# Balancer.net
KiCad netlist of a schematic drawn in Altium Designer
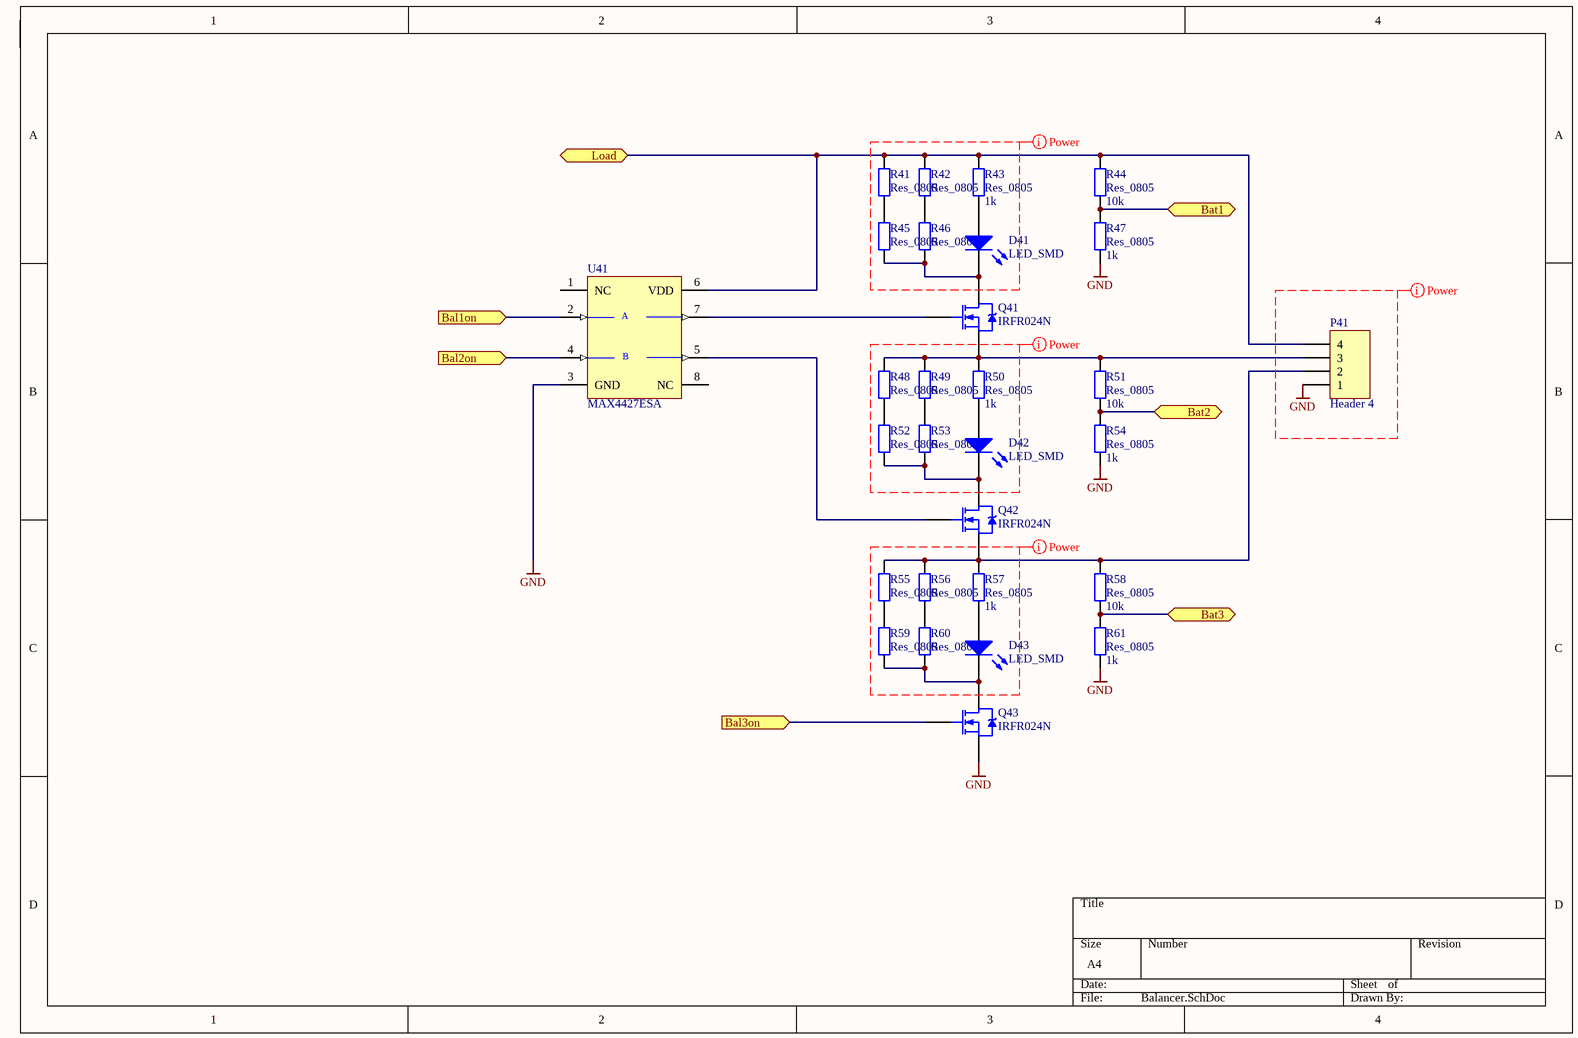
[diagram p0: Balancer.SchDoc]

(export (version "E")
  (design (tool "Eeschema 10.0.6"))
  (components
    (comp (ref "D41") (value "LED_SMD") (footprint "LED_SMD") (libsource (lib "Diodes$") (part "DIODE_48")))
    (comp (ref "D42") (value "LED_SMD") (footprint "LED_SMD") (libsource (lib "Diodes$") (part "DIODE_48")))
    (comp (ref "D43") (value "LED_SMD") (footprint "LED_SMD") (libsource (lib "Diodes$") (part "DIODE_48")))
    (comp (ref "P41") (value "Header 4") (footprint "HDR1X4") (libsource (lib "Connectors$") (part "Con_33")))
    (comp (ref "Q41")
      (value "IRFR024N")
      (footprint "TO-252AA_N")
      (description "HEXFET N-Channel Power MOSFET")
      (fields (field (name "PUBLISHER") "Altium Limited"))
      (libsource (lib "IR Discrete MOSFET - Power") (part "IRFR024N"))
    )
    (comp (ref "Q42")
      (value "IRFR024N")
      (footprint "TO-252AA_N")
      (description "HEXFET N-Channel Power MOSFET")
      (fields (field (name "PUBLISHER") "Altium Limited"))
      (libsource (lib "IR Discrete MOSFET - Power") (part "IRFR024N"))
    )
    (comp (ref "Q43")
      (value "IRFR024N")
      (footprint "TO-252AA_N")
      (description "HEXFET N-Channel Power MOSFET")
      (fields (field (name "PUBLISHER") "Altium Limited"))
      (libsource (lib "IR Discrete MOSFET - Power") (part "IRFR024N"))
    )
    (comp (ref "R41") (value "Res_0805") (footprint "_0805") (libsource (lib "Resistors$") (part "Res_6")))
    (comp (ref "R42") (value "Res_0805") (footprint "_0805") (libsource (lib "Resistors$") (part "Res_6")))
    (comp (ref "R43")
      (value "Res_0805")
      (footprint "_0805")
      (fields (field (name "ALTIUM_VALUE") "1k"))
      (libsource (lib "Resistors$") (part "Res_6"))
    )
    (comp (ref "R44")
      (value "Res_0805")
      (footprint "_0805")
      (fields (field (name "ALTIUM_VALUE") "10k"))
      (libsource (lib "Resistors$") (part "Res_6"))
    )
    (comp (ref "R45") (value "Res_0805") (footprint "_0805") (libsource (lib "Resistors$") (part "Res_6")))
    (comp (ref "R46") (value "Res_0805") (footprint "_0805") (libsource (lib "Resistors$") (part "Res_6")))
    (comp (ref "R47")
      (value "Res_0805")
      (footprint "_0805")
      (fields (field (name "ALTIUM_VALUE") "1k"))
      (libsource (lib "Resistors$") (part "Res_6"))
    )
    (comp (ref "R48") (value "Res_0805") (footprint "_0805") (libsource (lib "Resistors$") (part "Res_6")))
    (comp (ref "R49") (value "Res_0805") (footprint "_0805") (libsource (lib "Resistors$") (part "Res_6")))
    (comp (ref "R50")
      (value "Res_0805")
      (footprint "_0805")
      (fields (field (name "ALTIUM_VALUE") "1k"))
      (libsource (lib "Resistors$") (part "Res_6"))
    )
    (comp (ref "R51")
      (value "Res_0805")
      (footprint "_0805")
      (fields (field (name "ALTIUM_VALUE") "10k"))
      (libsource (lib "Resistors$") (part "Res_6"))
    )
    (comp (ref "R52") (value "Res_0805") (footprint "_0805") (libsource (lib "Resistors$") (part "Res_6")))
    (comp (ref "R53") (value "Res_0805") (footprint "_0805") (libsource (lib "Resistors$") (part "Res_6")))
    (comp (ref "R54")
      (value "Res_0805")
      (footprint "_0805")
      (fields (field (name "ALTIUM_VALUE") "1k"))
      (libsource (lib "Resistors$") (part "Res_6"))
    )
    (comp (ref "R55") (value "Res_0805") (footprint "_0805") (libsource (lib "Resistors$") (part "Res_6")))
    (comp (ref "R56") (value "Res_0805") (footprint "_0805") (libsource (lib "Resistors$") (part "Res_6")))
    (comp (ref "R57")
      (value "Res_0805")
      (footprint "_0805")
      (fields (field (name "ALTIUM_VALUE") "1k"))
      (libsource (lib "Resistors$") (part "Res_6"))
    )
    (comp (ref "R58")
      (value "Res_0805")
      (footprint "_0805")
      (fields (field (name "ALTIUM_VALUE") "10k"))
      (libsource (lib "Resistors$") (part "Res_6"))
    )
    (comp (ref "R59") (value "Res_0805") (footprint "_0805") (libsource (lib "Resistors$") (part "Res_6")))
    (comp (ref "R60") (value "Res_0805") (footprint "_0805") (libsource (lib "Resistors$") (part "Res_6")))
    (comp (ref "R61")
      (value "Res_0805")
      (footprint "_0805")
      (fields (field (name "ALTIUM_VALUE") "1k"))
      (libsource (lib "Resistors$") (part "Res_6"))
    )
    (comp (ref "U41")
      (value "MAX4427ESA")
      (footprint "NSO8_N")
      (description "Dual High-Speed 1.5A MOSFET Driver")
      (fields (field (name "PUBLISHER") "Altium Limited"))
      (libsource (lib "Maxim Interface MOSFET Driver") (part "MAX4427ESA"))
    )
  )
  (nets
    (net (code "1") (name "/Bal1on") (class "Default")
      (node (ref "U41") (pin "2") (pinfunction "INA_2") (pintype "input"))
    )
    (net (code "2") (name "/Bal2on") (class "Default")
      (node (ref "U41") (pin "4") (pinfunction "INB_4") (pintype "input"))
    )
    (net (code "3") (name "/Bal3on") (class "Default")
      (node (ref "Q43") (pin "1") (pinfunction "G_1") (pintype "passive"))
    )
    (net (code "4") (name "/Bat1") (class "Default")
      (node (ref "R44") (pin "1") (pinfunction "1_1") (pintype "passive"))
      (node (ref "R47") (pin "2") (pinfunction "2_2") (pintype "passive"))
    )
    (net (code "5") (name "/Bat2") (class "Default")
      (node (ref "R51") (pin "1") (pinfunction "1_1") (pintype "passive"))
      (node (ref "R54") (pin "2") (pinfunction "2_2") (pintype "passive"))
    )
    (net (code "6") (name "/Bat3") (class "Default")
      (node (ref "R58") (pin "1") (pinfunction "1_1") (pintype "passive"))
      (node (ref "R61") (pin "2") (pinfunction "2_2") (pintype "passive"))
    )
    (net (code "7") (name "/Load") (class "Default")
      (node (ref "P41") (pin "4") (pinfunction "4_4") (pintype "passive"))
      (node (ref "R41") (pin "2") (pinfunction "2_2") (pintype "passive"))
      (node (ref "R42") (pin "2") (pinfunction "2_2") (pintype "passive"))
      (node (ref "R43") (pin "2") (pinfunction "2_2") (pintype "passive"))
      (node (ref "R44") (pin "2") (pinfunction "2_2") (pintype "passive"))
      (node (ref "U41") (pin "6") (pinfunction "VDD_6") (pintype "power_in"))
    )
    (net (code "8") (name "GND") (class "Default")
      (node (ref "P41") (pin "1") (pinfunction "1_1") (pintype "passive"))
      (node (ref "Q43") (pin "3") (pinfunction "S_3") (pintype "passive"))
      (node (ref "R47") (pin "1") (pinfunction "1_1") (pintype "passive"))
      (node (ref "R54") (pin "1") (pinfunction "1_1") (pintype "passive"))
      (node (ref "R61") (pin "1") (pinfunction "1_1") (pintype "passive"))
      (node (ref "U41") (pin "3") (pinfunction "GND_3") (pintype "power_in"))
    )
    (net (code "9") (name "Net-(D41-Pad1)") (class "Default")
      (node (ref "D41") (pin "1") (pinfunction "1_1") (pintype "passive"))
      (node (ref "R43") (pin "1") (pinfunction "1_1") (pintype "passive"))
    )
    (net (code "10") (name "Net-(D42-Pad1)") (class "Default")
      (node (ref "D42") (pin "1") (pinfunction "1_1") (pintype "passive"))
      (node (ref "R50") (pin "1") (pinfunction "1_1") (pintype "passive"))
    )
    (net (code "11") (name "Net-(D43-Pad1)") (class "Default")
      (node (ref "D43") (pin "1") (pinfunction "1_1") (pintype "passive"))
      (node (ref "R57") (pin "1") (pinfunction "1_1") (pintype "passive"))
    )
    (net (code "12") (name "Net-(Q41-D)") (class "Default")
      (node (ref "D41") (pin "2") (pinfunction "2_2") (pintype "passive"))
      (node (ref "Q41") (pin "4") (pinfunction "D_4") (pintype "passive"))
      (node (ref "R45") (pin "1") (pinfunction "1_1") (pintype "passive"))
      (node (ref "R46") (pin "1") (pinfunction "1_1") (pintype "passive"))
    )
    (net (code "13") (name "Net-(Q41-G)") (class "Default")
      (node (ref "Q41") (pin "1") (pinfunction "G_1") (pintype "passive"))
      (node (ref "U41") (pin "7") (pinfunction "OUTA_7") (pintype "output"))
    )
    (net (code "14") (name "Net-(Q41-S)") (class "Default")
      (node (ref "P41") (pin "3") (pinfunction "3_3") (pintype "passive"))
      (node (ref "Q41") (pin "3") (pinfunction "S_3") (pintype "passive"))
      (node (ref "R48") (pin "2") (pinfunction "2_2") (pintype "passive"))
      (node (ref "R49") (pin "2") (pinfunction "2_2") (pintype "passive"))
      (node (ref "R50") (pin "2") (pinfunction "2_2") (pintype "passive"))
      (node (ref "R51") (pin "2") (pinfunction "2_2") (pintype "passive"))
    )
    (net (code "15") (name "Net-(Q42-D)") (class "Default")
      (node (ref "D42") (pin "2") (pinfunction "2_2") (pintype "passive"))
      (node (ref "Q42") (pin "4") (pinfunction "D_4") (pintype "passive"))
      (node (ref "R52") (pin "1") (pinfunction "1_1") (pintype "passive"))
      (node (ref "R53") (pin "1") (pinfunction "1_1") (pintype "passive"))
    )
    (net (code "16") (name "Net-(Q42-G)") (class "Default")
      (node (ref "Q42") (pin "1") (pinfunction "G_1") (pintype "passive"))
      (node (ref "U41") (pin "5") (pinfunction "OUTB_5") (pintype "output"))
    )
    (net (code "17") (name "Net-(Q42-S)") (class "Default")
      (node (ref "P41") (pin "2") (pinfunction "2_2") (pintype "passive"))
      (node (ref "Q42") (pin "3") (pinfunction "S_3") (pintype "passive"))
      (node (ref "R55") (pin "2") (pinfunction "2_2") (pintype "passive"))
      (node (ref "R56") (pin "2") (pinfunction "2_2") (pintype "passive"))
      (node (ref "R57") (pin "2") (pinfunction "2_2") (pintype "passive"))
      (node (ref "R58") (pin "2") (pinfunction "2_2") (pintype "passive"))
    )
    (net (code "18") (name "Net-(Q43-D)") (class "Default")
      (node (ref "D43") (pin "2") (pinfunction "2_2") (pintype "passive"))
      (node (ref "Q43") (pin "4") (pinfunction "D_4") (pintype "passive"))
      (node (ref "R59") (pin "1") (pinfunction "1_1") (pintype "passive"))
      (node (ref "R60") (pin "1") (pinfunction "1_1") (pintype "passive"))
    )
    (net (code "19") (name "Net-(R41-Pad1)") (class "Default")
      (node (ref "R41") (pin "1") (pinfunction "1_1") (pintype "passive"))
      (node (ref "R45") (pin "2") (pinfunction "2_2") (pintype "passive"))
    )
    (net (code "20") (name "Net-(R42-Pad1)") (class "Default")
      (node (ref "R42") (pin "1") (pinfunction "1_1") (pintype "passive"))
      (node (ref "R46") (pin "2") (pinfunction "2_2") (pintype "passive"))
    )
    (net (code "21") (name "Net-(R48-Pad1)") (class "Default")
      (node (ref "R48") (pin "1") (pinfunction "1_1") (pintype "passive"))
      (node (ref "R52") (pin "2") (pinfunction "2_2") (pintype "passive"))
    )
    (net (code "22") (name "Net-(R49-Pad1)") (class "Default")
      (node (ref "R49") (pin "1") (pinfunction "1_1") (pintype "passive"))
      (node (ref "R53") (pin "2") (pinfunction "2_2") (pintype "passive"))
    )
    (net (code "23") (name "Net-(R55-Pad1)") (class "Default")
      (node (ref "R55") (pin "1") (pinfunction "1_1") (pintype "passive"))
      (node (ref "R59") (pin "2") (pinfunction "2_2") (pintype "passive"))
    )
    (net (code "24") (name "Net-(R56-Pad1)") (class "Default")
      (node (ref "R56") (pin "1") (pinfunction "1_1") (pintype "passive"))
      (node (ref "R60") (pin "2") (pinfunction "2_2") (pintype "passive"))
    )
    (net (code "25") (name "unconnected-(U41-NC-Pad1)") (class "Default")
      (node (ref "U41") (pin "1") (pinfunction "NC_1") (pintype "passive"))
    )
    (net (code "26") (name "unconnected-(U41-NC-Pad8)") (class "Default")
      (node (ref "U41") (pin "8") (pinfunction "NC_8") (pintype "passive"))
    )
  )
)
